# SCH_PCB-micropad_2024-07-04.net
KiCad netlist of a schematic drawn in EasyEDA
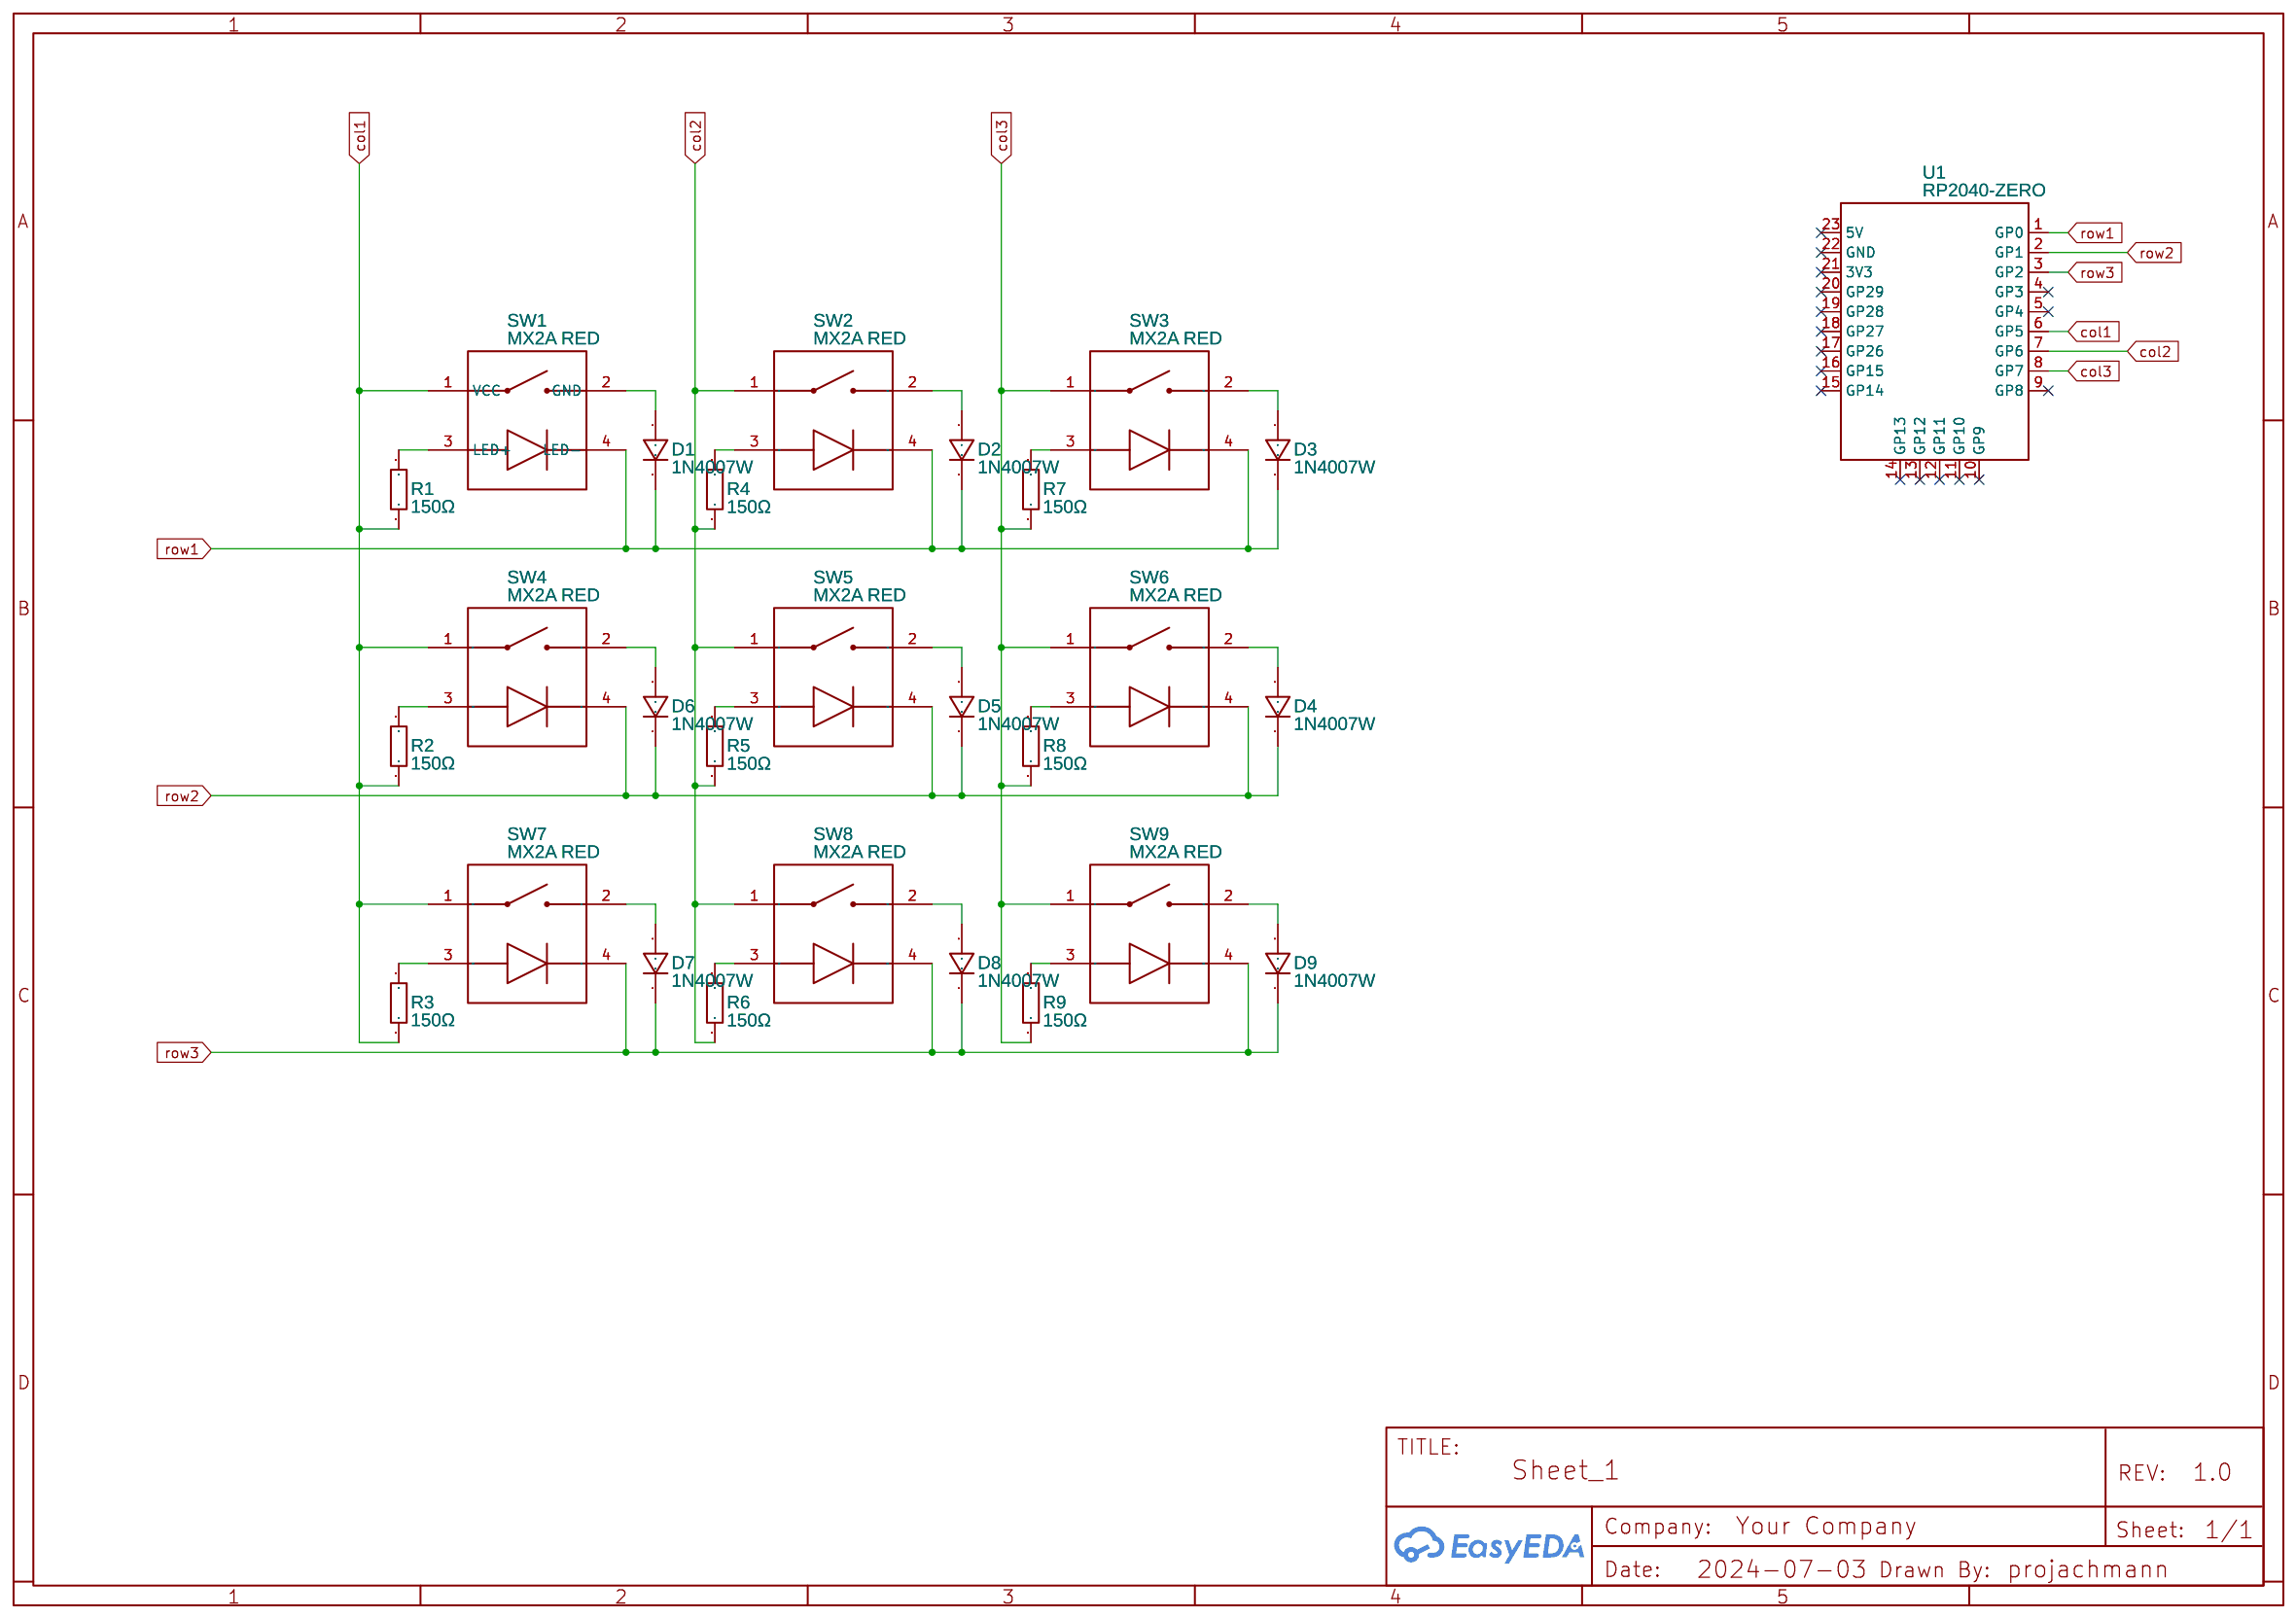
[diagram p0: schematic sheet]

(export (version "E")
  (design (tool "Eeschema 10.0.6"))
  (components
    (comp (ref "D1")
      (value "1N4007W")
      (fields (field (name "Manufacturer") "BLUE ROCKET"))
      (libsource (lib "") (part "1N4007W"))
    )
    (comp (ref "D2")
      (value "1N4007W")
      (fields (field (name "Manufacturer") "BLUE ROCKET"))
      (libsource (lib "") (part "1N4007W"))
    )
    (comp (ref "D3")
      (value "1N4007W")
      (fields (field (name "Manufacturer") "BLUE ROCKET"))
      (libsource (lib "") (part "1N4007W"))
    )
    (comp (ref "D4")
      (value "1N4007W")
      (fields (field (name "Manufacturer") "BLUE ROCKET"))
      (libsource (lib "") (part "1N4007W"))
    )
    (comp (ref "D5")
      (value "1N4007W")
      (fields (field (name "Manufacturer") "BLUE ROCKET"))
      (libsource (lib "") (part "1N4007W"))
    )
    (comp (ref "D6")
      (value "1N4007W")
      (fields (field (name "Manufacturer") "BLUE ROCKET"))
      (libsource (lib "") (part "1N4007W"))
    )
    (comp (ref "D7")
      (value "1N4007W")
      (fields (field (name "Manufacturer") "BLUE ROCKET"))
      (libsource (lib "") (part "1N4007W"))
    )
    (comp (ref "D8")
      (value "1N4007W")
      (fields (field (name "Manufacturer") "BLUE ROCKET"))
      (libsource (lib "") (part "1N4007W"))
    )
    (comp (ref "D9")
      (value "1N4007W")
      (fields (field (name "Manufacturer") "BLUE ROCKET"))
      (libsource (lib "") (part "1N4007W"))
    )
    (comp (ref "R1")
      (value "150Ω")
      (fields (field (name "Manufacturer Part") "MFR1WSFTE52-150R") (field (name "Manufacturer") "YAGEO(国巨)"))
      (libsource (lib "") (part "MFR1WSFTE52-150R"))
    )
    (comp (ref "R2")
      (value "150Ω")
      (fields (field (name "Manufacturer Part") "MFR1WSFTE52-150R") (field (name "Manufacturer") "YAGEO(国巨)"))
      (libsource (lib "") (part "MFR1WSFTE52-150R"))
    )
    (comp (ref "R3")
      (value "150Ω")
      (fields (field (name "Manufacturer Part") "MFR1WSFTE52-150R") (field (name "Manufacturer") "YAGEO(国巨)"))
      (libsource (lib "") (part "MFR1WSFTE52-150R"))
    )
    (comp (ref "R4")
      (value "150Ω")
      (fields (field (name "Manufacturer Part") "MFR1WSFTE52-150R") (field (name "Manufacturer") "YAGEO(国巨)"))
      (libsource (lib "") (part "MFR1WSFTE52-150R"))
    )
    (comp (ref "R5")
      (value "150Ω")
      (fields (field (name "Manufacturer Part") "MFR1WSFTE52-150R") (field (name "Manufacturer") "YAGEO(国巨)"))
      (libsource (lib "") (part "MFR1WSFTE52-150R"))
    )
    (comp (ref "R6")
      (value "150Ω")
      (fields (field (name "Manufacturer Part") "MFR1WSFTE52-150R") (field (name "Manufacturer") "YAGEO(国巨)"))
      (libsource (lib "") (part "MFR1WSFTE52-150R"))
    )
    (comp (ref "R7")
      (value "150Ω")
      (fields (field (name "Manufacturer Part") "MFR1WSFTE52-150R") (field (name "Manufacturer") "YAGEO(国巨)"))
      (libsource (lib "") (part "MFR1WSFTE52-150R"))
    )
    (comp (ref "R8")
      (value "150Ω")
      (fields (field (name "Manufacturer Part") "MFR1WSFTE52-150R") (field (name "Manufacturer") "YAGEO(国巨)"))
      (libsource (lib "") (part "MFR1WSFTE52-150R"))
    )
    (comp (ref "R9")
      (value "150Ω")
      (fields (field (name "Manufacturer Part") "MFR1WSFTE52-150R") (field (name "Manufacturer") "YAGEO(国巨)"))
      (libsource (lib "") (part "MFR1WSFTE52-150R"))
    )
    (comp (ref "SW1")
      (value "MX2A RED")
      (fields (field (name "Manufacturer Part") "MX2A-L1NB") (field (name "Manufacturer") "Cherry"))
      (libsource (lib "") (part "MX2A RED"))
    )
    (comp (ref "SW2")
      (value "MX2A RED")
      (fields (field (name "Manufacturer Part") "MX2A-L1NB") (field (name "Manufacturer") "Cherry"))
      (libsource (lib "") (part "MX2A RED"))
    )
    (comp (ref "SW3")
      (value "MX2A RED")
      (fields (field (name "Manufacturer Part") "MX2A-L1NB") (field (name "Manufacturer") "Cherry"))
      (libsource (lib "") (part "MX2A RED"))
    )
    (comp (ref "SW4")
      (value "MX2A RED")
      (fields (field (name "Manufacturer Part") "MX2A-L1NB") (field (name "Manufacturer") "Cherry"))
      (libsource (lib "") (part "MX2A RED"))
    )
    (comp (ref "SW5")
      (value "MX2A RED")
      (fields (field (name "Manufacturer Part") "MX2A-L1NB") (field (name "Manufacturer") "Cherry"))
      (libsource (lib "") (part "MX2A RED"))
    )
    (comp (ref "SW6")
      (value "MX2A RED")
      (fields (field (name "Manufacturer Part") "MX2A-L1NB") (field (name "Manufacturer") "Cherry"))
      (libsource (lib "") (part "MX2A RED"))
    )
    (comp (ref "SW7")
      (value "MX2A RED")
      (fields (field (name "Manufacturer Part") "MX2A-L1NB") (field (name "Manufacturer") "Cherry"))
      (libsource (lib "") (part "MX2A RED"))
    )
    (comp (ref "SW8")
      (value "MX2A RED")
      (fields (field (name "Manufacturer Part") "MX2A-L1NB") (field (name "Manufacturer") "Cherry"))
      (libsource (lib "") (part "MX2A RED"))
    )
    (comp (ref "SW9")
      (value "MX2A RED")
      (fields (field (name "Manufacturer Part") "MX2A-L1NB") (field (name "Manufacturer") "Cherry"))
      (libsource (lib "") (part "MX2A RED"))
    )
    (comp (ref "U1")
      (value "RP2040-ZERO")
      (fields
        (field (name "Manufacturer Part") "RP2040-Zero")
        (field (name "Manufacturer") "Waveshare(微雪电子)")
      )
      (libsource (lib "") (part "RP2040-ZERO"))
    )
  )
  (nets
    (net (code "1") (name "Net-(SW1-GND)") (class "Default")
      (node (ref "D1") (pin "2") (pinfunction "2_2") (pintype "unspecified"))
      (node (ref "SW1") (pin "2") (pinfunction "GND_2") (pintype "unspecified"))
    )
    (net (code "2") (name "Net-(SW1-LED+)") (class "Default")
      (node (ref "R1") (pin "2") (pinfunction "2_2") (pintype "unspecified"))
      (node (ref "SW1") (pin "3") (pinfunction "LED+_3") (pintype "unspecified"))
    )
    (net (code "3") (name "Net-(SW2-GND)") (class "Default")
      (node (ref "D2") (pin "2") (pinfunction "2_2") (pintype "unspecified"))
      (node (ref "SW2") (pin "2") (pinfunction "GND_2") (pintype "unspecified"))
    )
    (net (code "4") (name "Net-(SW2-LED+)") (class "Default")
      (node (ref "R4") (pin "2") (pinfunction "2_2") (pintype "unspecified"))
      (node (ref "SW2") (pin "3") (pinfunction "LED+_3") (pintype "unspecified"))
    )
    (net (code "5") (name "Net-(SW3-GND)") (class "Default")
      (node (ref "D3") (pin "2") (pinfunction "2_2") (pintype "unspecified"))
      (node (ref "SW3") (pin "2") (pinfunction "GND_2") (pintype "unspecified"))
    )
    (net (code "6") (name "Net-(SW3-LED+)") (class "Default")
      (node (ref "R7") (pin "2") (pinfunction "2_2") (pintype "unspecified"))
      (node (ref "SW3") (pin "3") (pinfunction "LED+_3") (pintype "unspecified"))
    )
    (net (code "7") (name "Net-(SW4-GND)") (class "Default")
      (node (ref "D6") (pin "2") (pinfunction "2_2") (pintype "unspecified"))
      (node (ref "SW4") (pin "2") (pinfunction "GND_2") (pintype "unspecified"))
    )
    (net (code "8") (name "Net-(SW4-LED+)") (class "Default")
      (node (ref "R2") (pin "2") (pinfunction "2_2") (pintype "unspecified"))
      (node (ref "SW4") (pin "3") (pinfunction "LED+_3") (pintype "unspecified"))
    )
    (net (code "9") (name "Net-(SW5-GND)") (class "Default")
      (node (ref "D5") (pin "2") (pinfunction "2_2") (pintype "unspecified"))
      (node (ref "SW5") (pin "2") (pinfunction "GND_2") (pintype "unspecified"))
    )
    (net (code "10") (name "Net-(SW5-LED+)") (class "Default")
      (node (ref "R5") (pin "2") (pinfunction "2_2") (pintype "unspecified"))
      (node (ref "SW5") (pin "3") (pinfunction "LED+_3") (pintype "unspecified"))
    )
    (net (code "11") (name "Net-(SW6-GND)") (class "Default")
      (node (ref "D4") (pin "2") (pinfunction "2_2") (pintype "unspecified"))
      (node (ref "SW6") (pin "2") (pinfunction "GND_2") (pintype "unspecified"))
    )
    (net (code "12") (name "Net-(SW6-LED+)") (class "Default")
      (node (ref "R8") (pin "2") (pinfunction "2_2") (pintype "unspecified"))
      (node (ref "SW6") (pin "3") (pinfunction "LED+_3") (pintype "unspecified"))
    )
    (net (code "13") (name "Net-(SW7-GND)") (class "Default")
      (node (ref "D7") (pin "2") (pinfunction "2_2") (pintype "unspecified"))
      (node (ref "SW7") (pin "2") (pinfunction "GND_2") (pintype "unspecified"))
    )
    (net (code "14") (name "Net-(SW7-LED+)") (class "Default")
      (node (ref "R3") (pin "2") (pinfunction "2_2") (pintype "unspecified"))
      (node (ref "SW7") (pin "3") (pinfunction "LED+_3") (pintype "unspecified"))
    )
    (net (code "15") (name "Net-(SW8-GND)") (class "Default")
      (node (ref "D8") (pin "2") (pinfunction "2_2") (pintype "unspecified"))
      (node (ref "SW8") (pin "2") (pinfunction "GND_2") (pintype "unspecified"))
    )
    (net (code "16") (name "Net-(SW8-LED+)") (class "Default")
      (node (ref "R6") (pin "2") (pinfunction "2_2") (pintype "unspecified"))
      (node (ref "SW8") (pin "3") (pinfunction "LED+_3") (pintype "unspecified"))
    )
    (net (code "17") (name "Net-(SW9-GND)") (class "Default")
      (node (ref "D9") (pin "2") (pinfunction "2_2") (pintype "unspecified"))
      (node (ref "SW9") (pin "2") (pinfunction "GND_2") (pintype "unspecified"))
    )
    (net (code "18") (name "Net-(SW9-LED+)") (class "Default")
      (node (ref "R9") (pin "2") (pinfunction "2_2") (pintype "unspecified"))
      (node (ref "SW9") (pin "3") (pinfunction "LED+_3") (pintype "unspecified"))
    )
    (net (code "19") (name "col1") (class "Default")
      (node (ref "R1") (pin "1") (pinfunction "1_1") (pintype "unspecified"))
      (node (ref "R2") (pin "1") (pinfunction "1_1") (pintype "unspecified"))
      (node (ref "R3") (pin "1") (pinfunction "1_1") (pintype "unspecified"))
      (node (ref "SW1") (pin "1") (pinfunction "VCC_1") (pintype "unspecified"))
      (node (ref "SW4") (pin "1") (pinfunction "VCC_1") (pintype "unspecified"))
      (node (ref "SW7") (pin "1") (pinfunction "VCC_1") (pintype "unspecified"))
      (node (ref "U1") (pin "6") (pinfunction "GP5_6") (pintype "unspecified"))
    )
    (net (code "20") (name "col2") (class "Default")
      (node (ref "R4") (pin "1") (pinfunction "1_1") (pintype "unspecified"))
      (node (ref "R5") (pin "1") (pinfunction "1_1") (pintype "unspecified"))
      (node (ref "R6") (pin "1") (pinfunction "1_1") (pintype "unspecified"))
      (node (ref "SW2") (pin "1") (pinfunction "VCC_1") (pintype "unspecified"))
      (node (ref "SW5") (pin "1") (pinfunction "VCC_1") (pintype "unspecified"))
      (node (ref "SW8") (pin "1") (pinfunction "VCC_1") (pintype "unspecified"))
      (node (ref "U1") (pin "7") (pinfunction "GP6_7") (pintype "unspecified"))
    )
    (net (code "21") (name "col3") (class "Default")
      (node (ref "R7") (pin "1") (pinfunction "1_1") (pintype "unspecified"))
      (node (ref "R8") (pin "1") (pinfunction "1_1") (pintype "unspecified"))
      (node (ref "R9") (pin "1") (pinfunction "1_1") (pintype "unspecified"))
      (node (ref "SW3") (pin "1") (pinfunction "VCC_1") (pintype "unspecified"))
      (node (ref "SW6") (pin "1") (pinfunction "VCC_1") (pintype "unspecified"))
      (node (ref "SW9") (pin "1") (pinfunction "VCC_1") (pintype "unspecified"))
      (node (ref "U1") (pin "8") (pinfunction "GP7_8") (pintype "unspecified"))
    )
    (net (code "22") (name "row1") (class "Default")
      (node (ref "D1") (pin "1") (pinfunction "1_1") (pintype "unspecified"))
      (node (ref "D2") (pin "1") (pinfunction "1_1") (pintype "unspecified"))
      (node (ref "D3") (pin "1") (pinfunction "1_1") (pintype "unspecified"))
      (node (ref "SW1") (pin "4") (pinfunction "LED-_4") (pintype "unspecified"))
      (node (ref "SW2") (pin "4") (pinfunction "LED-_4") (pintype "unspecified"))
      (node (ref "SW3") (pin "4") (pinfunction "LED-_4") (pintype "unspecified"))
      (node (ref "U1") (pin "1") (pinfunction "GP0_1") (pintype "unspecified"))
    )
    (net (code "23") (name "row2") (class "Default")
      (node (ref "D4") (pin "1") (pinfunction "1_1") (pintype "unspecified"))
      (node (ref "D5") (pin "1") (pinfunction "1_1") (pintype "unspecified"))
      (node (ref "D6") (pin "1") (pinfunction "1_1") (pintype "unspecified"))
      (node (ref "SW4") (pin "4") (pinfunction "LED-_4") (pintype "unspecified"))
      (node (ref "SW5") (pin "4") (pinfunction "LED-_4") (pintype "unspecified"))
      (node (ref "SW6") (pin "4") (pinfunction "LED-_4") (pintype "unspecified"))
      (node (ref "U1") (pin "2") (pinfunction "GP1_2") (pintype "unspecified"))
    )
    (net (code "24") (name "row3") (class "Default")
      (node (ref "D7") (pin "1") (pinfunction "1_1") (pintype "unspecified"))
      (node (ref "D8") (pin "1") (pinfunction "1_1") (pintype "unspecified"))
      (node (ref "D9") (pin "1") (pinfunction "1_1") (pintype "unspecified"))
      (node (ref "SW7") (pin "4") (pinfunction "LED-_4") (pintype "unspecified"))
      (node (ref "SW8") (pin "4") (pinfunction "LED-_4") (pintype "unspecified"))
      (node (ref "SW9") (pin "4") (pinfunction "LED-_4") (pintype "unspecified"))
      (node (ref "U1") (pin "3") (pinfunction "GP2_3") (pintype "unspecified"))
    )
    (net (code "25") (name "unconnected-(U1-3V3-Pad21)") (class "Default")
      (node (ref "U1") (pin "21") (pinfunction "3V3_21") (pintype "unspecified+no_connect"))
    )
    (net (code "26") (name "unconnected-(U1-5V-Pad23)") (class "Default")
      (node (ref "U1") (pin "23") (pinfunction "5V_23") (pintype "unspecified+no_connect"))
    )
    (net (code "27") (name "unconnected-(U1-GND-Pad22)") (class "Default")
      (node (ref "U1") (pin "22") (pinfunction "GND_22") (pintype "unspecified+no_connect"))
    )
    (net (code "28") (name "unconnected-(U1-GP3-Pad4)") (class "Default")
      (node (ref "U1") (pin "4") (pinfunction "GP3_4") (pintype "unspecified+no_connect"))
    )
    (net (code "29") (name "unconnected-(U1-GP4-Pad5)") (class "Default")
      (node (ref "U1") (pin "5") (pinfunction "GP4_5") (pintype "unspecified+no_connect"))
    )
    (net (code "30") (name "unconnected-(U1-GP8-Pad9)") (class "Default")
      (node (ref "U1") (pin "9") (pinfunction "GP8_9") (pintype "unspecified+no_connect"))
    )
    (net (code "31") (name "unconnected-(U1-GP9-Pad10)") (class "Default")
      (node (ref "U1") (pin "10") (pinfunction "GP9_10") (pintype "unspecified+no_connect"))
    )
    (net (code "32") (name "unconnected-(U1-GP10-Pad11)") (class "Default")
      (node (ref "U1") (pin "11") (pinfunction "GP10_11") (pintype "unspecified+no_connect"))
    )
    (net (code "33") (name "unconnected-(U1-GP11-Pad12)") (class "Default")
      (node (ref "U1") (pin "12") (pinfunction "GP11_12") (pintype "unspecified+no_connect"))
    )
    (net (code "34") (name "unconnected-(U1-GP12-Pad13)") (class "Default")
      (node (ref "U1") (pin "13") (pinfunction "GP12_13") (pintype "unspecified+no_connect"))
    )
    (net (code "35") (name "unconnected-(U1-GP13-Pad14)") (class "Default")
      (node (ref "U1") (pin "14") (pinfunction "GP13_14") (pintype "unspecified+no_connect"))
    )
    (net (code "36") (name "unconnected-(U1-GP14-Pad15)") (class "Default")
      (node (ref "U1") (pin "15") (pinfunction "GP14_15") (pintype "unspecified+no_connect"))
    )
    (net (code "37") (name "unconnected-(U1-GP15-Pad16)") (class "Default")
      (node (ref "U1") (pin "16") (pinfunction "GP15_16") (pintype "unspecified+no_connect"))
    )
    (net (code "38") (name "unconnected-(U1-GP26-Pad17)") (class "Default")
      (node (ref "U1") (pin "17") (pinfunction "GP26_17") (pintype "unspecified+no_connect"))
    )
    (net (code "39") (name "unconnected-(U1-GP27-Pad18)") (class "Default")
      (node (ref "U1") (pin "18") (pinfunction "GP27_18") (pintype "unspecified+no_connect"))
    )
    (net (code "40") (name "unconnected-(U1-GP28-Pad19)") (class "Default")
      (node (ref "U1") (pin "19") (pinfunction "GP28_19") (pintype "unspecified+no_connect"))
    )
    (net (code "41") (name "unconnected-(U1-GP29-Pad20)") (class "Default")
      (node (ref "U1") (pin "20") (pinfunction "GP29_20") (pintype "unspecified+no_connect"))
    )
  )
)
